# 05_-_Sensors.net
KiCad netlist of a schematic drawn in Altium Designer
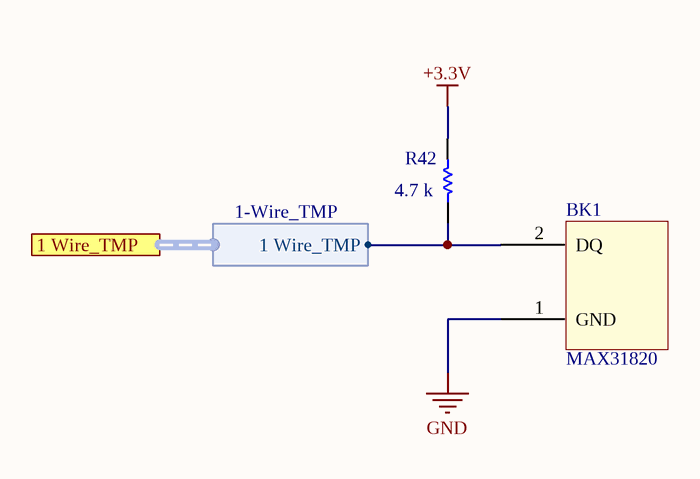
[diagram p0: [05] - Sensors.SchDoc]

(export (version "E")
  (design (tool "Eeschema 10.0.6"))
  (components
    (comp (ref "BK1")
      (value "MAX31820")
      (description "MAX31820PAR  temper sensor")
      (libsource (lib "Blue Tractor-2021") (part "MAX31820"))
    )
    (comp (ref "R42")
      (value "Res1")
      (footprint "Res-0603")
      (description "Chip Resistor")
      (fields
        (field (name "MANUFACTURER") "Panasonic")
        (field (name "MANUFACTURER PART NUMBER") "ERJ-3GEYJ103V")
        (field (name "RESISTANCE") "4.7 k")
      )
      (libsource (lib "Altium_Library") (part "Res1"))
    )
  )
  (nets
    (net (code "2") (name "+3.3V") (class "Default")
      (node (ref "R42") (pin "2") (pinfunction "2_2") (pintype "passive"))
    )
    (net (code "4") (name "GND") (class "Default")
      (node (ref "BK1") (pin "1") (pinfunction "GND_1") (pintype "power_in"))
    )
    (net (code "5") (name "Net-(BK1-DQ)") (class "Default")
      (node (ref "BK1") (pin "2") (pinfunction "DQ_2") (pintype "power_in"))
      (node (ref "R42") (pin "1") (pinfunction "1_1") (pintype "passive"))
    )
  )
)
